# NN22_7Lvl_ResSrcAdapter02_s00.net
KiCad netlist of a schematic drawn in EAGLE
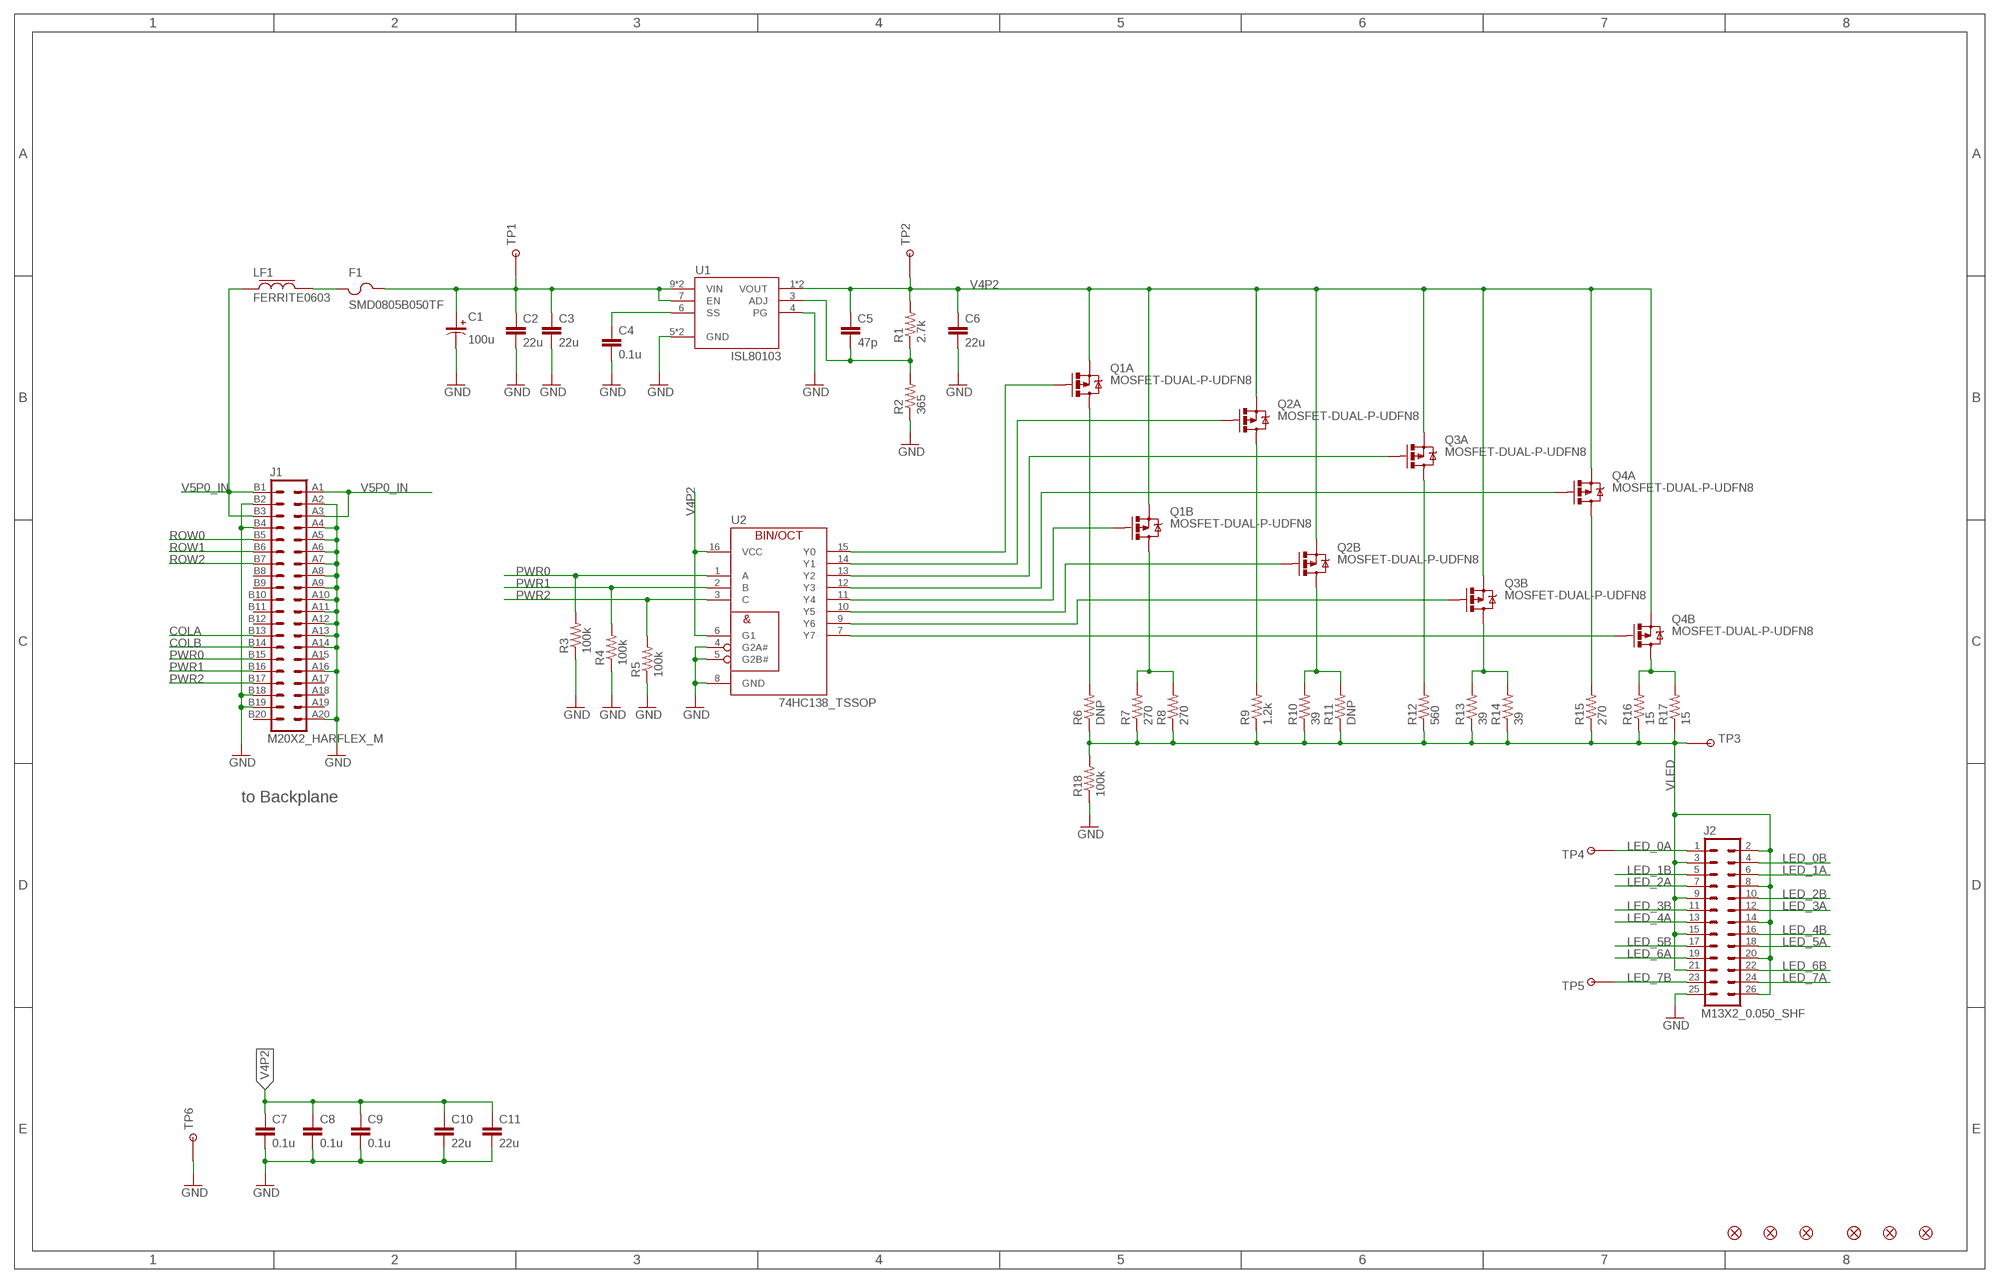
[diagram p0: schematic, sheet 1]
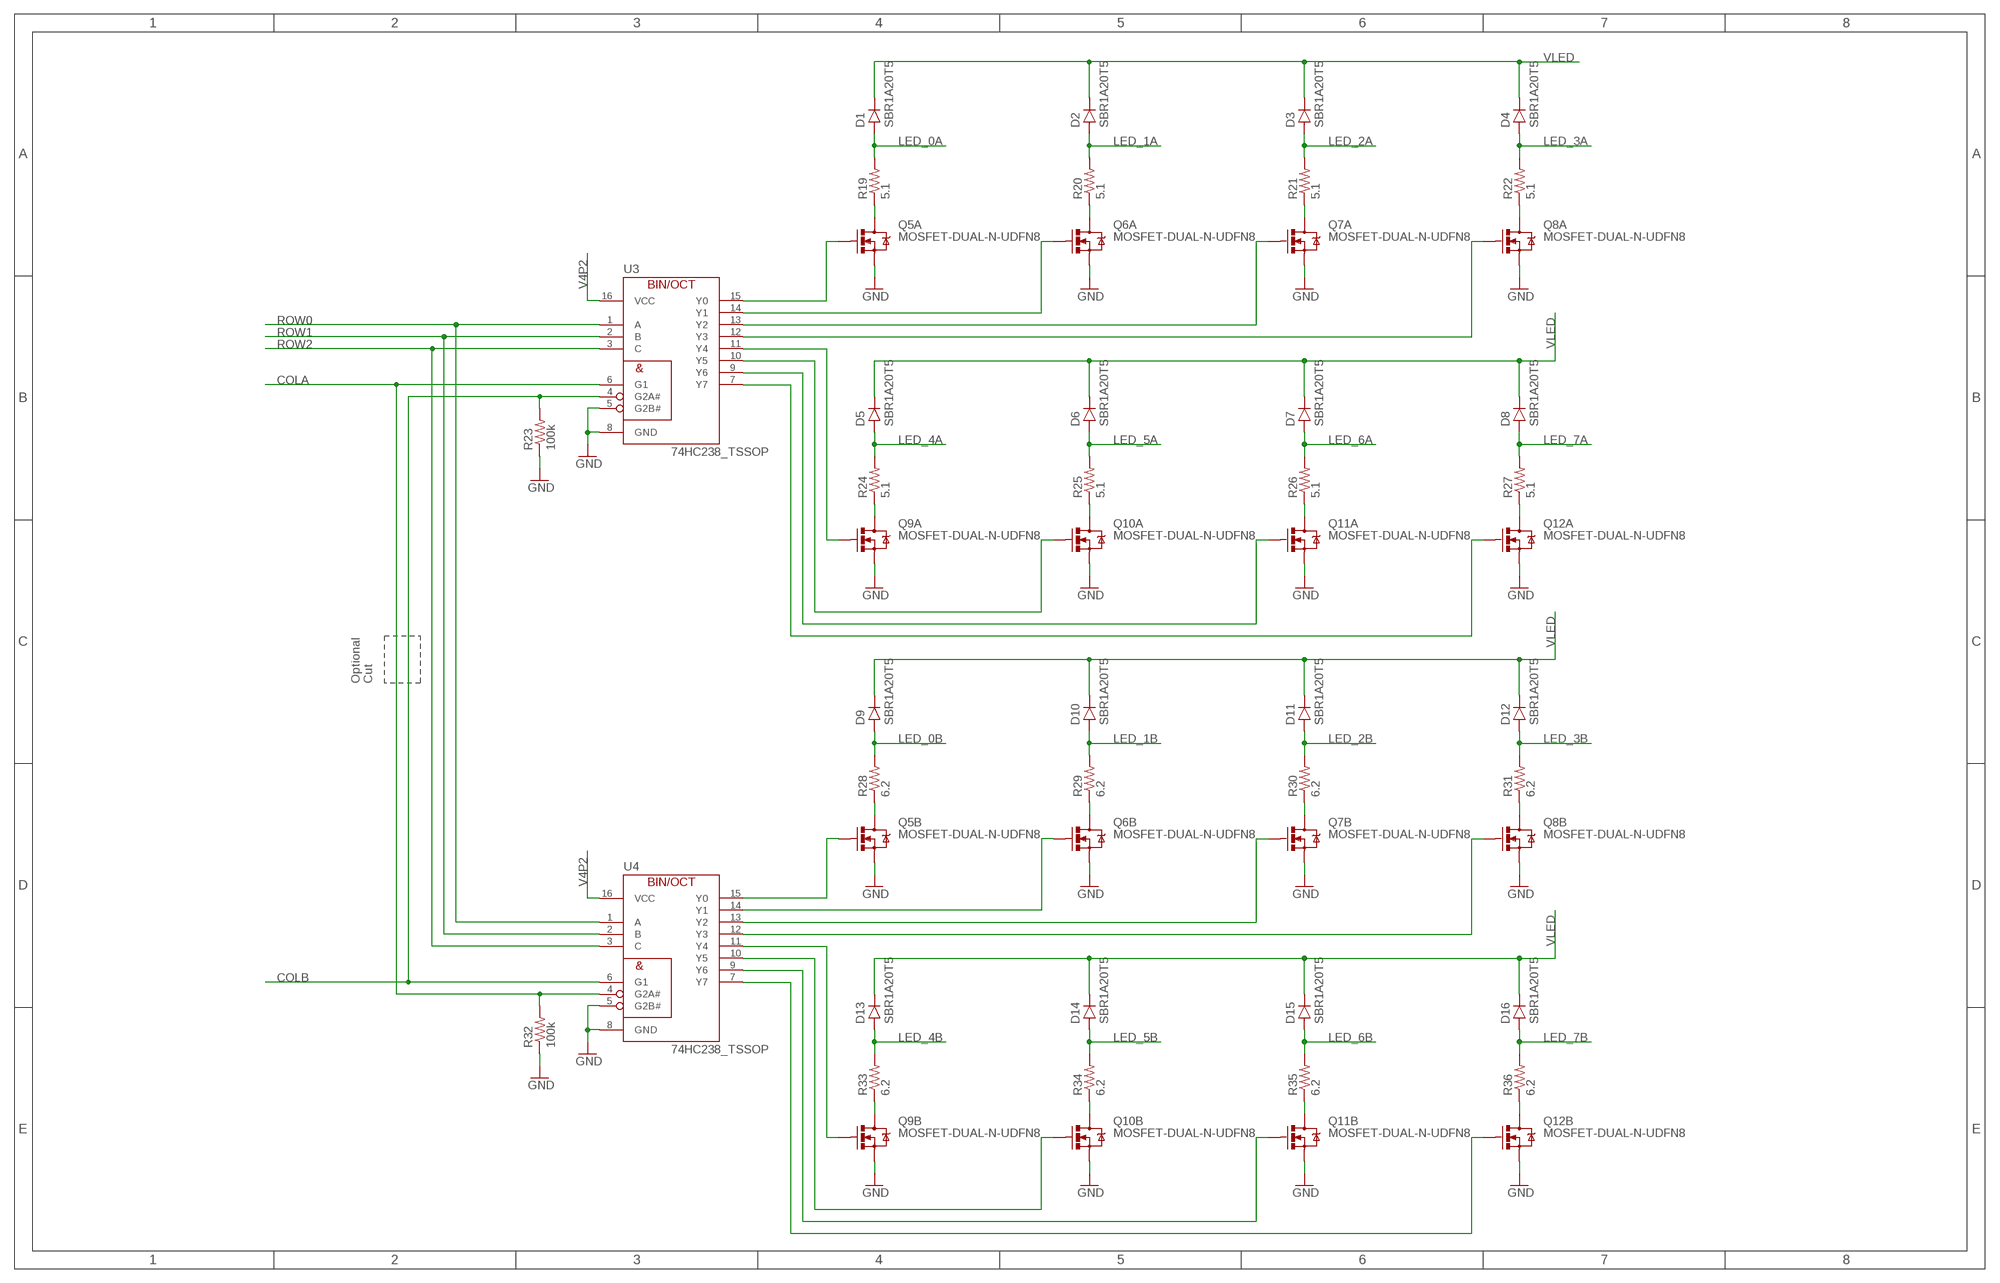
[diagram p1: schematic, sheet 2]

(export (version "E")
  (design (tool "Eeschema 10.0.6"))
  (components
    (comp (ref "D1")
      (value "SBR1A20T5")
      (footprint "eagle-import:SOD523")
      (libsource (lib "eagle-import") (part "DIODE_SOD523"))
    )
    (comp (ref "D2")
      (value "SBR1A20T5")
      (footprint "eagle-import:SOD523")
      (libsource (lib "eagle-import") (part "DIODE_SOD523"))
    )
    (comp (ref "D3")
      (value "SBR1A20T5")
      (footprint "eagle-import:SOD523")
      (libsource (lib "eagle-import") (part "DIODE_SOD523"))
    )
    (comp (ref "D4")
      (value "SBR1A20T5")
      (footprint "eagle-import:SOD523")
      (libsource (lib "eagle-import") (part "DIODE_SOD523"))
    )
    (comp (ref "D5")
      (value "SBR1A20T5")
      (footprint "eagle-import:SOD523")
      (libsource (lib "eagle-import") (part "DIODE_SOD523"))
    )
    (comp (ref "D6")
      (value "SBR1A20T5")
      (footprint "eagle-import:SOD523")
      (libsource (lib "eagle-import") (part "DIODE_SOD523"))
    )
    (comp (ref "D7")
      (value "SBR1A20T5")
      (footprint "eagle-import:SOD523")
      (libsource (lib "eagle-import") (part "DIODE_SOD523"))
    )
    (comp (ref "D8")
      (value "SBR1A20T5")
      (footprint "eagle-import:SOD523")
      (libsource (lib "eagle-import") (part "DIODE_SOD523"))
    )
    (comp (ref "D9")
      (value "SBR1A20T5")
      (footprint "eagle-import:SOD523")
      (libsource (lib "eagle-import") (part "DIODE_SOD523"))
    )
    (comp (ref "D10")
      (value "SBR1A20T5")
      (footprint "eagle-import:SOD523")
      (libsource (lib "eagle-import") (part "DIODE_SOD523"))
    )
    (comp (ref "D11")
      (value "SBR1A20T5")
      (footprint "eagle-import:SOD523")
      (libsource (lib "eagle-import") (part "DIODE_SOD523"))
    )
    (comp (ref "D12")
      (value "SBR1A20T5")
      (footprint "eagle-import:SOD523")
      (libsource (lib "eagle-import") (part "DIODE_SOD523"))
    )
    (comp (ref "D13")
      (value "SBR1A20T5")
      (footprint "eagle-import:SOD523")
      (libsource (lib "eagle-import") (part "DIODE_SOD523"))
    )
    (comp (ref "D14")
      (value "SBR1A20T5")
      (footprint "eagle-import:SOD523")
      (libsource (lib "eagle-import") (part "DIODE_SOD523"))
    )
    (comp (ref "D15")
      (value "SBR1A20T5")
      (footprint "eagle-import:SOD523")
      (libsource (lib "eagle-import") (part "DIODE_SOD523"))
    )
    (comp (ref "D16")
      (value "SBR1A20T5")
      (footprint "eagle-import:SOD523")
      (libsource (lib "eagle-import") (part "DIODE_SOD523"))
    )
    (comp (ref "Q5")
      (value "MOSFET-DUAL-N-UDFN8")
      (footprint "eagle-import:UDFN8")
      (libsource (lib "eagle-import") (part "MOSFET-DUAL-N-UDFN8"))
    )
    (comp (ref "Q6")
      (value "MOSFET-DUAL-N-UDFN8")
      (footprint "eagle-import:UDFN8")
      (libsource (lib "eagle-import") (part "MOSFET-DUAL-N-UDFN8"))
    )
    (comp (ref "Q7")
      (value "MOSFET-DUAL-N-UDFN8")
      (footprint "eagle-import:UDFN8")
      (libsource (lib "eagle-import") (part "MOSFET-DUAL-N-UDFN8"))
    )
    (comp (ref "Q8")
      (value "MOSFET-DUAL-N-UDFN8")
      (footprint "eagle-import:UDFN8")
      (libsource (lib "eagle-import") (part "MOSFET-DUAL-N-UDFN8"))
    )
    (comp (ref "Q9")
      (value "MOSFET-DUAL-N-UDFN8")
      (footprint "eagle-import:UDFN8")
      (libsource (lib "eagle-import") (part "MOSFET-DUAL-N-UDFN8"))
    )
    (comp (ref "Q10")
      (value "MOSFET-DUAL-N-UDFN8")
      (footprint "eagle-import:UDFN8")
      (libsource (lib "eagle-import") (part "MOSFET-DUAL-N-UDFN8"))
    )
    (comp (ref "Q11")
      (value "MOSFET-DUAL-N-UDFN8")
      (footprint "eagle-import:UDFN8")
      (libsource (lib "eagle-import") (part "MOSFET-DUAL-N-UDFN8"))
    )
    (comp (ref "Q12")
      (value "MOSFET-DUAL-N-UDFN8")
      (footprint "eagle-import:UDFN8")
      (libsource (lib "eagle-import") (part "MOSFET-DUAL-N-UDFN8"))
    )
    (comp (ref "R19")
      (value "5.1")
      (footprint "eagle-import:0805")
      (libsource (lib "eagle-import") (part "RESISTOR0805-RES"))
    )
    (comp (ref "R20")
      (value "5.1")
      (footprint "eagle-import:0805")
      (libsource (lib "eagle-import") (part "RESISTOR0805-RES"))
    )
    (comp (ref "R21")
      (value "5.1")
      (footprint "eagle-import:0805")
      (libsource (lib "eagle-import") (part "RESISTOR0805-RES"))
    )
    (comp (ref "R22")
      (value "5.1")
      (footprint "eagle-import:0805")
      (libsource (lib "eagle-import") (part "RESISTOR0805-RES"))
    )
    (comp (ref "R23")
      (value "100k")
      (footprint "eagle-import:0402-RES")
      (libsource (lib "eagle-import") (part "RESISTOR0402-RES"))
    )
    (comp (ref "R24")
      (value "5.1")
      (footprint "eagle-import:0805")
      (libsource (lib "eagle-import") (part "RESISTOR0805-RES"))
    )
    (comp (ref "R25")
      (value "5.1")
      (footprint "eagle-import:0805")
      (libsource (lib "eagle-import") (part "RESISTOR0805-RES"))
    )
    (comp (ref "R26")
      (value "5.1")
      (footprint "eagle-import:0805")
      (libsource (lib "eagle-import") (part "RESISTOR0805-RES"))
    )
    (comp (ref "R27")
      (value "5.1")
      (footprint "eagle-import:0805")
      (libsource (lib "eagle-import") (part "RESISTOR0805-RES"))
    )
    (comp (ref "R28")
      (value "6.2")
      (footprint "eagle-import:0805")
      (libsource (lib "eagle-import") (part "RESISTOR0805-RES"))
    )
    (comp (ref "R29")
      (value "6.2")
      (footprint "eagle-import:0805")
      (libsource (lib "eagle-import") (part "RESISTOR0805-RES"))
    )
    (comp (ref "R30")
      (value "6.2")
      (footprint "eagle-import:0805")
      (libsource (lib "eagle-import") (part "RESISTOR0805-RES"))
    )
    (comp (ref "R31")
      (value "6.2")
      (footprint "eagle-import:0805")
      (libsource (lib "eagle-import") (part "RESISTOR0805-RES"))
    )
    (comp (ref "R32")
      (value "100k")
      (footprint "eagle-import:0402-RES")
      (libsource (lib "eagle-import") (part "RESISTOR0402-RES"))
    )
    (comp (ref "R33")
      (value "6.2")
      (footprint "eagle-import:0805")
      (libsource (lib "eagle-import") (part "RESISTOR0805-RES"))
    )
    (comp (ref "R34")
      (value "6.2")
      (footprint "eagle-import:0805")
      (libsource (lib "eagle-import") (part "RESISTOR0805-RES"))
    )
    (comp (ref "R35")
      (value "6.2")
      (footprint "eagle-import:0805")
      (libsource (lib "eagle-import") (part "RESISTOR0805-RES"))
    )
    (comp (ref "R36")
      (value "6.2")
      (footprint "eagle-import:0805")
      (libsource (lib "eagle-import") (part "RESISTOR0805-RES"))
    )
    (comp (ref "U3")
      (value "74HC238_TSSOP")
      (footprint "eagle-import:TSSOP16")
      (libsource (lib "eagle-import") (part "74HC238_TSSOP"))
    )
    (comp (ref "U4")
      (value "74HC238_TSSOP")
      (footprint "eagle-import:TSSOP16")
      (libsource (lib "eagle-import") (part "74HC238_TSSOP"))
    )
    (comp (ref "C1")
      (value "100u")
      (footprint "eagle-import:2917-CAP")
      (libsource (lib "eagle-import") (part "CAP-POL2917"))
    )
    (comp (ref "C2")
      (value "22u")
      (footprint "eagle-import:1206")
      (libsource (lib "eagle-import") (part "CAP1206"))
    )
    (comp (ref "C3")
      (value "22u")
      (footprint "eagle-import:1206")
      (libsource (lib "eagle-import") (part "CAP1206"))
    )
    (comp (ref "C4")
      (value "0.1u")
      (footprint "eagle-import:0402-CAP")
      (libsource (lib "eagle-import") (part "CAP0402-CAP"))
    )
    (comp (ref "C5")
      (value "47p")
      (footprint "eagle-import:0402-CAP")
      (libsource (lib "eagle-import") (part "CAP0402-CAP"))
    )
    (comp (ref "C6")
      (value "22u")
      (footprint "eagle-import:1206")
      (libsource (lib "eagle-import") (part "CAP1206"))
    )
    (comp (ref "C7")
      (value "0.1u")
      (footprint "eagle-import:0402-CAP")
      (libsource (lib "eagle-import") (part "CAP0402-CAP"))
    )
    (comp (ref "C8")
      (value "0.1u")
      (footprint "eagle-import:0402-CAP")
      (libsource (lib "eagle-import") (part "CAP0402-CAP"))
    )
    (comp (ref "C9")
      (value "0.1u")
      (footprint "eagle-import:0402-CAP")
      (libsource (lib "eagle-import") (part "CAP0402-CAP"))
    )
    (comp (ref "C10")
      (value "22u")
      (footprint "eagle-import:1206")
      (libsource (lib "eagle-import") (part "CAP1206"))
    )
    (comp (ref "C11")
      (value "22u")
      (footprint "eagle-import:1206")
      (libsource (lib "eagle-import") (part "CAP1206"))
    )
    (comp (ref "F1")
      (value "SMD0805B050TF")
      (footprint "eagle-import:0805")
      (libsource (lib "eagle-import") (part "FUSE_0805"))
    )
    (comp (ref "FID1")
      (value "FIDUCIALUFIDUCIAL")
      (footprint "eagle-import:MICRO-FIDUCIAL")
      (libsource (lib "eagle-import") (part "FIDUCIALUFIDUCIAL"))
    )
    (comp (ref "FID2")
      (value "FIDUCIALUFIDUCIAL")
      (footprint "eagle-import:MICRO-FIDUCIAL")
      (libsource (lib "eagle-import") (part "FIDUCIALUFIDUCIAL"))
    )
    (comp (ref "FID3")
      (value "FIDUCIALUFIDUCIAL")
      (footprint "eagle-import:MICRO-FIDUCIAL")
      (libsource (lib "eagle-import") (part "FIDUCIALUFIDUCIAL"))
    )
    (comp (ref "FID4")
      (value "FIDUCIALUFIDUCIAL")
      (footprint "eagle-import:MICRO-FIDUCIAL")
      (libsource (lib "eagle-import") (part "FIDUCIALUFIDUCIAL"))
    )
    (comp (ref "FID5")
      (value "FIDUCIALUFIDUCIAL")
      (footprint "eagle-import:MICRO-FIDUCIAL")
      (libsource (lib "eagle-import") (part "FIDUCIALUFIDUCIAL"))
    )
    (comp (ref "FID6")
      (value "FIDUCIALUFIDUCIAL")
      (footprint "eagle-import:MICRO-FIDUCIAL")
      (libsource (lib "eagle-import") (part "FIDUCIALUFIDUCIAL"))
    )
    (comp (ref "J1")
      (value "M20X2_HARFLEX_M")
      (footprint "eagle-import:M20X2_HARFLEX_M")
      (libsource (lib "eagle-import") (part "M20X2_HARFLEX_M"))
    )
    (comp (ref "J2")
      (value "M13X2_0.050_SHF")
      (footprint "eagle-import:M13X2_0.050_SHF")
      (libsource (lib "eagle-import") (part "M13X2_0.050_SHF"))
    )
    (comp (ref "LF1")
      (value "FERRITE0603")
      (footprint "eagle-import:0603-FER")
      (libsource (lib "eagle-import") (part "FERRITE0603"))
    )
    (comp (ref "Q1")
      (value "MOSFET-DUAL-P-UDFN8")
      (footprint "eagle-import:UDFN8")
      (libsource (lib "eagle-import") (part "MOSFET-DUAL-P-UDFN8"))
    )
    (comp (ref "Q2")
      (value "MOSFET-DUAL-P-UDFN8")
      (footprint "eagle-import:UDFN8")
      (libsource (lib "eagle-import") (part "MOSFET-DUAL-P-UDFN8"))
    )
    (comp (ref "Q3")
      (value "MOSFET-DUAL-P-UDFN8")
      (footprint "eagle-import:UDFN8")
      (libsource (lib "eagle-import") (part "MOSFET-DUAL-P-UDFN8"))
    )
    (comp (ref "Q4")
      (value "MOSFET-DUAL-P-UDFN8")
      (footprint "eagle-import:UDFN8")
      (libsource (lib "eagle-import") (part "MOSFET-DUAL-P-UDFN8"))
    )
    (comp (ref "R1")
      (value "2.7k")
      (footprint "eagle-import:0402-RES")
      (libsource (lib "eagle-import") (part "RESISTOR0402-RES"))
    )
    (comp (ref "R2")
      (value "365")
      (footprint "eagle-import:0402-RES")
      (libsource (lib "eagle-import") (part "RESISTOR0402-RES"))
    )
    (comp (ref "R3")
      (value "100k")
      (footprint "eagle-import:0402-RES")
      (libsource (lib "eagle-import") (part "RESISTOR0402-RES"))
    )
    (comp (ref "R4")
      (value "100k")
      (footprint "eagle-import:0402-RES")
      (libsource (lib "eagle-import") (part "RESISTOR0402-RES"))
    )
    (comp (ref "R5")
      (value "100k")
      (footprint "eagle-import:0402-RES")
      (libsource (lib "eagle-import") (part "RESISTOR0402-RES"))
    )
    (comp (ref "R6")
      (value "DNP")
      (footprint "eagle-import:0805")
      (libsource (lib "eagle-import") (part "RESISTOR0805-RES"))
    )
    (comp (ref "R7")
      (value "270")
      (footprint "eagle-import:0805")
      (libsource (lib "eagle-import") (part "RESISTOR0805-RES"))
    )
    (comp (ref "R8")
      (value "270")
      (footprint "eagle-import:0805")
      (libsource (lib "eagle-import") (part "RESISTOR0805-RES"))
    )
    (comp (ref "R9")
      (value "1.2k")
      (footprint "eagle-import:0805")
      (libsource (lib "eagle-import") (part "RESISTOR0805-RES"))
    )
    (comp (ref "R10")
      (value "39")
      (footprint "eagle-import:0805")
      (libsource (lib "eagle-import") (part "RESISTOR0805-RES"))
    )
    (comp (ref "R11")
      (value "DNP")
      (footprint "eagle-import:0805")
      (libsource (lib "eagle-import") (part "RESISTOR0805-RES"))
    )
    (comp (ref "R12")
      (value "560")
      (footprint "eagle-import:0805")
      (libsource (lib "eagle-import") (part "RESISTOR0805-RES"))
    )
    (comp (ref "R13")
      (value "39")
      (footprint "eagle-import:0805")
      (libsource (lib "eagle-import") (part "RESISTOR0805-RES"))
    )
    (comp (ref "R14")
      (value "39")
      (footprint "eagle-import:0805")
      (libsource (lib "eagle-import") (part "RESISTOR0805-RES"))
    )
    (comp (ref "R15")
      (value "270")
      (footprint "eagle-import:0805")
      (libsource (lib "eagle-import") (part "RESISTOR0805-RES"))
    )
    (comp (ref "R16")
      (value "15")
      (footprint "eagle-import:0805")
      (libsource (lib "eagle-import") (part "RESISTOR0805-RES"))
    )
    (comp (ref "R17")
      (value "15")
      (footprint "eagle-import:0805")
      (libsource (lib "eagle-import") (part "RESISTOR0805-RES"))
    )
    (comp (ref "R18")
      (value "100k")
      (footprint "eagle-import:0402-RES")
      (libsource (lib "eagle-import") (part "RESISTOR0402-RES"))
    )
    (comp (ref "TP1")
      (value "TESTPOINT_ROUND")
      (footprint "eagle-import:TESTPAD_ROUND")
      (libsource (lib "eagle-import") (part "TESTPOINT_ROUND"))
    )
    (comp (ref "TP2")
      (value "TESTPOINT_ROUND")
      (footprint "eagle-import:TESTPAD_ROUND")
      (libsource (lib "eagle-import") (part "TESTPOINT_ROUND"))
    )
    (comp (ref "TP3")
      (value "TESTPOINT_ROUND")
      (footprint "eagle-import:TESTPAD_ROUND")
      (libsource (lib "eagle-import") (part "TESTPOINT_ROUND"))
    )
    (comp (ref "TP4")
      (value "TESTPOINT_ROUND")
      (footprint "eagle-import:TESTPAD_ROUND")
      (libsource (lib "eagle-import") (part "TESTPOINT_ROUND"))
    )
    (comp (ref "TP5")
      (value "TESTPOINT_ROUND")
      (footprint "eagle-import:TESTPAD_ROUND")
      (libsource (lib "eagle-import") (part "TESTPOINT_ROUND"))
    )
    (comp (ref "TP6")
      (value "TESTPOINT1X01")
      (footprint "eagle-import:1X01")
      (libsource (lib "eagle-import") (part "TESTPOINT1X01"))
    )
    (comp (ref "U1")
      (value "ISL80103")
      (footprint "eagle-import:DFN10_ISL")
      (libsource (lib "eagle-import") (part "ISL80103"))
    )
    (comp (ref "U2")
      (value "74HC138_TSSOP")
      (footprint "eagle-import:TSSOP16")
      (libsource (lib "eagle-import") (part "74HC138_TSSOP"))
    )
  )
  (nets
    (net (code "1") (name "COLA") (class "Default")
      (node (ref "J1") (pin "B13") (pinfunction "25_B13") (pintype "passive"))
      (node (ref "R32") (pin "2") (pinfunction "2_2") (pintype "passive"))
      (node (ref "U3") (pin "6") (pinfunction "G1_6") (pintype "input"))
      (node (ref "U4") (pin "4") (pinfunction "G2A#_4") (pintype "input"))
    )
    (net (code "2") (name "COLB") (class "Default")
      (node (ref "J1") (pin "B14") (pinfunction "27_B14") (pintype "passive"))
      (node (ref "R23") (pin "2") (pinfunction "2_2") (pintype "passive"))
      (node (ref "U3") (pin "4") (pinfunction "G2A#_4") (pintype "input"))
      (node (ref "U4") (pin "6") (pinfunction "G1_6") (pintype "input"))
    )
    (net (code "3") (name "GND") (class "Default")
      (node (ref "C1") (pin "N") (pinfunction "N_N") (pintype "passive"))
      (node (ref "C10") (pin "2") (pinfunction "2_2") (pintype "passive"))
      (node (ref "C11") (pin "2") (pinfunction "2_2") (pintype "passive"))
      (node (ref "C2") (pin "2") (pinfunction "2_2") (pintype "passive"))
      (node (ref "C3") (pin "2") (pinfunction "2_2") (pintype "passive"))
      (node (ref "C4") (pin "2") (pinfunction "2_2") (pintype "passive"))
      (node (ref "C6") (pin "2") (pinfunction "2_2") (pintype "passive"))
      (node (ref "C7") (pin "2") (pinfunction "2_2") (pintype "passive"))
      (node (ref "C8") (pin "2") (pinfunction "2_2") (pintype "passive"))
      (node (ref "C9") (pin "2") (pinfunction "2_2") (pintype "passive"))
      (node (ref "J1") (pin "A10") (pinfunction "20_A10") (pintype "passive"))
      (node (ref "J1") (pin "A11") (pinfunction "22_A11") (pintype "passive"))
      (node (ref "J1") (pin "A12") (pinfunction "24_A12") (pintype "passive"))
      (node (ref "J1") (pin "A13") (pinfunction "26_A13") (pintype "passive"))
      (node (ref "J1") (pin "A14") (pinfunction "28_A14") (pintype "passive"))
      (node (ref "J1") (pin "A16") (pinfunction "32_A16") (pintype "passive"))
      (node (ref "J1") (pin "A2") (pinfunction "4_A2") (pintype "passive"))
      (node (ref "J1") (pin "A20") (pinfunction "40_A20") (pintype "passive"))
      (node (ref "J1") (pin "A4") (pinfunction "8_A4") (pintype "passive"))
      (node (ref "J1") (pin "A5") (pinfunction "10_A5") (pintype "passive"))
      (node (ref "J1") (pin "A6") (pinfunction "12_A6") (pintype "passive"))
      (node (ref "J1") (pin "A7") (pinfunction "14_A7") (pintype "passive"))
      (node (ref "J1") (pin "A8") (pinfunction "16_A8") (pintype "passive"))
      (node (ref "J1") (pin "A9") (pinfunction "18_A9") (pintype "passive"))
      (node (ref "J1") (pin "B18") (pinfunction "35_B18") (pintype "passive"))
      (node (ref "J1") (pin "B19") (pinfunction "37_B19") (pintype "passive"))
      (node (ref "J1") (pin "B2") (pinfunction "3_B2") (pintype "passive"))
      (node (ref "J1") (pin "B4") (pinfunction "7_B4") (pintype "passive"))
      (node (ref "J2") (pin "25") (pinfunction "25_25") (pintype "passive"))
      (node (ref "Q10") (pin "1") (pinfunction "S_1") (pintype "passive"))
      (node (ref "Q10") (pin "4") (pinfunction "S_4") (pintype "passive"))
      (node (ref "Q11") (pin "1") (pinfunction "S_1") (pintype "passive"))
      (node (ref "Q11") (pin "4") (pinfunction "S_4") (pintype "passive"))
      (node (ref "Q12") (pin "1") (pinfunction "S_1") (pintype "passive"))
      (node (ref "Q12") (pin "4") (pinfunction "S_4") (pintype "passive"))
      (node (ref "Q5") (pin "1") (pinfunction "S_1") (pintype "passive"))
      (node (ref "Q5") (pin "4") (pinfunction "S_4") (pintype "passive"))
      (node (ref "Q6") (pin "1") (pinfunction "S_1") (pintype "passive"))
      (node (ref "Q6") (pin "4") (pinfunction "S_4") (pintype "passive"))
      (node (ref "Q7") (pin "1") (pinfunction "S_1") (pintype "passive"))
      (node (ref "Q7") (pin "4") (pinfunction "S_4") (pintype "passive"))
      (node (ref "Q8") (pin "1") (pinfunction "S_1") (pintype "passive"))
      (node (ref "Q8") (pin "4") (pinfunction "S_4") (pintype "passive"))
      (node (ref "Q9") (pin "1") (pinfunction "S_1") (pintype "passive"))
      (node (ref "Q9") (pin "4") (pinfunction "S_4") (pintype "passive"))
      (node (ref "R18") (pin "1") (pinfunction "1_1") (pintype "passive"))
      (node (ref "R2") (pin "1") (pinfunction "1_1") (pintype "passive"))
      (node (ref "R23") (pin "1") (pinfunction "1_1") (pintype "passive"))
      (node (ref "R3") (pin "1") (pinfunction "1_1") (pintype "passive"))
      (node (ref "R32") (pin "1") (pinfunction "1_1") (pintype "passive"))
      (node (ref "R4") (pin "1") (pinfunction "1_1") (pintype "passive"))
      (node (ref "R5") (pin "1") (pinfunction "1_1") (pintype "passive"))
      (node (ref "TP6") (pin "1") (pinfunction "P$1_1") (pintype "bidirectional"))
      (node (ref "U1") (pin "4") (pinfunction "PG_4") (pintype "open_collector"))
      (node (ref "U1") (pin "5") (pinfunction "GND_5") (pintype "power_in"))
      (node (ref "U1") (pin "PAD") (pinfunction "GND_PAD") (pintype "power_in"))
      (node (ref "U2") (pin "4") (pinfunction "G2A#_4") (pintype "input"))
      (node (ref "U2") (pin "5") (pinfunction "G2B#_5") (pintype "input"))
      (node (ref "U2") (pin "8") (pinfunction "GND_8") (pintype "power_in"))
      (node (ref "U3") (pin "5") (pinfunction "G2B#_5") (pintype "input"))
      (node (ref "U3") (pin "8") (pinfunction "GND_8") (pintype "power_in"))
      (node (ref "U4") (pin "5") (pinfunction "G2B#_5") (pintype "input"))
      (node (ref "U4") (pin "8") (pinfunction "GND_8") (pintype "power_in"))
    )
    (net (code "4") (name "LED_0A") (class "Default")
      (node (ref "D1") (pin "A") (pinfunction "A_A") (pintype "bidirectional"))
      (node (ref "J2") (pin "1") (pinfunction "1_1") (pintype "passive"))
      (node (ref "R19") (pin "2") (pinfunction "2_2") (pintype "passive"))
      (node (ref "TP4") (pin "P$1") (pinfunction "P$1_P$1") (pintype "bidirectional"))
    )
    (net (code "5") (name "LED_0B") (class "Default")
      (node (ref "D9") (pin "A") (pinfunction "A_A") (pintype "bidirectional"))
      (node (ref "J2") (pin "4") (pinfunction "4_4") (pintype "passive"))
      (node (ref "R28") (pin "2") (pinfunction "2_2") (pintype "passive"))
    )
    (net (code "6") (name "LED_1A") (class "Default")
      (node (ref "D2") (pin "A") (pinfunction "A_A") (pintype "bidirectional"))
      (node (ref "J2") (pin "6") (pinfunction "6_6") (pintype "passive"))
      (node (ref "R20") (pin "2") (pinfunction "2_2") (pintype "passive"))
    )
    (net (code "7") (name "LED_1B") (class "Default")
      (node (ref "D10") (pin "A") (pinfunction "A_A") (pintype "bidirectional"))
      (node (ref "J2") (pin "5") (pinfunction "5_5") (pintype "passive"))
      (node (ref "R29") (pin "2") (pinfunction "2_2") (pintype "passive"))
    )
    (net (code "8") (name "LED_2A") (class "Default")
      (node (ref "D3") (pin "A") (pinfunction "A_A") (pintype "bidirectional"))
      (node (ref "J2") (pin "7") (pinfunction "7_7") (pintype "passive"))
      (node (ref "R21") (pin "2") (pinfunction "2_2") (pintype "passive"))
    )
    (net (code "9") (name "LED_2B") (class "Default")
      (node (ref "D11") (pin "A") (pinfunction "A_A") (pintype "bidirectional"))
      (node (ref "J2") (pin "10") (pinfunction "10_10") (pintype "passive"))
      (node (ref "R30") (pin "2") (pinfunction "2_2") (pintype "passive"))
    )
    (net (code "10") (name "LED_3A") (class "Default")
      (node (ref "D4") (pin "A") (pinfunction "A_A") (pintype "bidirectional"))
      (node (ref "J2") (pin "12") (pinfunction "12_12") (pintype "passive"))
      (node (ref "R22") (pin "2") (pinfunction "2_2") (pintype "passive"))
    )
    (net (code "11") (name "LED_3B") (class "Default")
      (node (ref "D12") (pin "A") (pinfunction "A_A") (pintype "bidirectional"))
      (node (ref "J2") (pin "11") (pinfunction "11_11") (pintype "passive"))
      (node (ref "R31") (pin "2") (pinfunction "2_2") (pintype "passive"))
    )
    (net (code "12") (name "LED_4A") (class "Default")
      (node (ref "D5") (pin "A") (pinfunction "A_A") (pintype "bidirectional"))
      (node (ref "J2") (pin "13") (pinfunction "13_13") (pintype "passive"))
      (node (ref "R24") (pin "2") (pinfunction "2_2") (pintype "passive"))
    )
    (net (code "13") (name "LED_4B") (class "Default")
      (node (ref "D13") (pin "A") (pinfunction "A_A") (pintype "bidirectional"))
      (node (ref "J2") (pin "16") (pinfunction "16_16") (pintype "passive"))
      (node (ref "R33") (pin "2") (pinfunction "2_2") (pintype "passive"))
    )
    (net (code "14") (name "LED_5A") (class "Default")
      (node (ref "D6") (pin "A") (pinfunction "A_A") (pintype "bidirectional"))
      (node (ref "J2") (pin "18") (pinfunction "18_18") (pintype "passive"))
      (node (ref "R25") (pin "2") (pinfunction "2_2") (pintype "passive"))
    )
    (net (code "15") (name "LED_5B") (class "Default")
      (node (ref "D14") (pin "A") (pinfunction "A_A") (pintype "bidirectional"))
      (node (ref "J2") (pin "17") (pinfunction "17_17") (pintype "passive"))
      (node (ref "R34") (pin "2") (pinfunction "2_2") (pintype "passive"))
    )
    (net (code "16") (name "LED_6A") (class "Default")
      (node (ref "D7") (pin "A") (pinfunction "A_A") (pintype "bidirectional"))
      (node (ref "J2") (pin "19") (pinfunction "19_19") (pintype "passive"))
      (node (ref "R26") (pin "2") (pinfunction "2_2") (pintype "passive"))
    )
    (net (code "17") (name "LED_6B") (class "Default")
      (node (ref "D15") (pin "A") (pinfunction "A_A") (pintype "bidirectional"))
      (node (ref "J2") (pin "22") (pinfunction "22_22") (pintype "passive"))
      (node (ref "R35") (pin "2") (pinfunction "2_2") (pintype "passive"))
    )
    (net (code "18") (name "LED_7A") (class "Default")
      (node (ref "D8") (pin "A") (pinfunction "A_A") (pintype "bidirectional"))
      (node (ref "J2") (pin "24") (pinfunction "24_24") (pintype "passive"))
      (node (ref "R27") (pin "2") (pinfunction "2_2") (pintype "passive"))
    )
    (net (code "19") (name "LED_7B") (class "Default")
      (node (ref "D16") (pin "A") (pinfunction "A_A") (pintype "bidirectional"))
      (node (ref "J2") (pin "23") (pinfunction "23_23") (pintype "passive"))
      (node (ref "R36") (pin "2") (pinfunction "2_2") (pintype "passive"))
      (node (ref "TP5") (pin "P$1") (pinfunction "P$1_P$1") (pintype "bidirectional"))
    )
    (net (code "20") (name "Net-(LF1-P$2)") (class "Default")
      (node (ref "F1") (pin "1") (pinfunction "1_1") (pintype "bidirectional"))
      (node (ref "LF1") (pin "2") (pinfunction "P$2_2") (pintype "bidirectional"))
    )
    (net (code "21") (name "Net-(Q1A-D-Pad6)") (class "Default")
      (node (ref "Q1") (pin "6") (pinfunction "D_6") (pintype "passive"))
      (node (ref "Q1") (pin "P1") (pinfunction "D_P1") (pintype "passive"))
      (node (ref "R6") (pin "2") (pinfunction "2_2") (pintype "passive"))
    )
    (net (code "22") (name "Net-(Q1A-G)") (class "Default")
      (node (ref "Q1") (pin "2") (pinfunction "G_2") (pintype "passive"))
      (node (ref "U2") (pin "15") (pinfunction "Y0_15") (pintype "output"))
    )
    (net (code "23") (name "Net-(Q1B-D-Pad3)") (class "Default")
      (node (ref "Q1") (pin "3") (pinfunction "D_3") (pintype "passive"))
      (node (ref "Q1") (pin "P2") (pinfunction "D_P2") (pintype "passive"))
      (node (ref "R7") (pin "2") (pinfunction "2_2") (pintype "passive"))
      (node (ref "R8") (pin "2") (pinfunction "2_2") (pintype "passive"))
    )
    (net (code "24") (name "Net-(Q1B-G)") (class "Default")
      (node (ref "Q1") (pin "5") (pinfunction "G_5") (pintype "passive"))
      (node (ref "U2") (pin "11") (pinfunction "Y4_11") (pintype "output"))
    )
    (net (code "25") (name "Net-(Q2A-D-Pad6)") (class "Default")
      (node (ref "Q2") (pin "6") (pinfunction "D_6") (pintype "passive"))
      (node (ref "Q2") (pin "P1") (pinfunction "D_P1") (pintype "passive"))
      (node (ref "R9") (pin "2") (pinfunction "2_2") (pintype "passive"))
    )
    (net (code "26") (name "Net-(Q2A-G)") (class "Default")
      (node (ref "Q2") (pin "2") (pinfunction "G_2") (pintype "passive"))
      (node (ref "U2") (pin "14") (pinfunction "Y1_14") (pintype "output"))
    )
    (net (code "27") (name "Net-(Q2B-D-Pad3)") (class "Default")
      (node (ref "Q2") (pin "3") (pinfunction "D_3") (pintype "passive"))
      (node (ref "Q2") (pin "P2") (pinfunction "D_P2") (pintype "passive"))
      (node (ref "R10") (pin "2") (pinfunction "2_2") (pintype "passive"))
      (node (ref "R11") (pin "2") (pinfunction "2_2") (pintype "passive"))
    )
    (net (code "28") (name "Net-(Q2B-G)") (class "Default")
      (node (ref "Q2") (pin "5") (pinfunction "G_5") (pintype "passive"))
      (node (ref "U2") (pin "10") (pinfunction "Y5_10") (pintype "output"))
    )
    (net (code "29") (name "Net-(Q3A-D-Pad6)") (class "Default")
      (node (ref "Q3") (pin "6") (pinfunction "D_6") (pintype "passive"))
      (node (ref "Q3") (pin "P1") (pinfunction "D_P1") (pintype "passive"))
      (node (ref "R12") (pin "2") (pinfunction "2_2") (pintype "passive"))
    )
    (net (code "30") (name "Net-(Q3A-G)") (class "Default")
      (node (ref "Q3") (pin "2") (pinfunction "G_2") (pintype "passive"))
      (node (ref "U2") (pin "13") (pinfunction "Y2_13") (pintype "output"))
    )
    (net (code "31") (name "Net-(Q3B-D-Pad3)") (class "Default")
      (node (ref "Q3") (pin "3") (pinfunction "D_3") (pintype "passive"))
      (node (ref "Q3") (pin "P2") (pinfunction "D_P2") (pintype "passive"))
      (node (ref "R13") (pin "2") (pinfunction "2_2") (pintype "passive"))
      (node (ref "R14") (pin "2") (pinfunction "2_2") (pintype "passive"))
    )
    (net (code "32") (name "Net-(Q3B-G)") (class "Default")
      (node (ref "Q3") (pin "5") (pinfunction "G_5") (pintype "passive"))
      (node (ref "U2") (pin "9") (pinfunction "Y6_9") (pintype "output"))
    )
    (net (code "33") (name "Net-(Q4A-D-Pad6)") (class "Default")
      (node (ref "Q4") (pin "6") (pinfunction "D_6") (pintype "passive"))
      (node (ref "Q4") (pin "P1") (pinfunction "D_P1") (pintype "passive"))
      (node (ref "R15") (pin "2") (pinfunction "2_2") (pintype "passive"))
    )
    (net (code "34") (name "Net-(Q4A-G)") (class "Default")
      (node (ref "Q4") (pin "2") (pinfunction "G_2") (pintype "passive"))
      (node (ref "U2") (pin "12") (pinfunction "Y3_12") (pintype "output"))
    )
    (net (code "35") (name "Net-(Q4B-D-Pad3)") (class "Default")
      (node (ref "Q4") (pin "3") (pinfunction "D_3") (pintype "passive"))
      (node (ref "Q4") (pin "P2") (pinfunction "D_P2") (pintype "passive"))
      (node (ref "R16") (pin "2") (pinfunction "2_2") (pintype "passive"))
      (node (ref "R17") (pin "2") (pinfunction "2_2") (pintype "passive"))
    )
    (net (code "36") (name "Net-(Q4B-G)") (class "Default")
      (node (ref "Q4") (pin "5") (pinfunction "G_5") (pintype "passive"))
      (node (ref "U2") (pin "7") (pinfunction "Y7_7") (pintype "output"))
    )
    (net (code "37") (name "Net-(Q5A-D-Pad6)") (class "Default")
      (node (ref "Q5") (pin "6") (pinfunction "D_6") (pintype "passive"))
      (node (ref "Q5") (pin "P1") (pinfunction "D_P1") (pintype "passive"))
      (node (ref "R19") (pin "1") (pinfunction "1_1") (pintype "passive"))
    )
    (net (code "38") (name "Net-(Q5A-G)") (class "Default")
      (node (ref "Q5") (pin "2") (pinfunction "G_2") (pintype "passive"))
      (node (ref "U3") (pin "15") (pinfunction "Y0_15") (pintype "output"))
    )
    (net (code "39") (name "Net-(Q5B-D-Pad3)") (class "Default")
      (node (ref "Q5") (pin "3") (pinfunction "D_3") (pintype "passive"))
      (node (ref "Q5") (pin "P2") (pinfunction "D_P2") (pintype "passive"))
      (node (ref "R28") (pin "1") (pinfunction "1_1") (pintype "passive"))
    )
    (net (code "40") (name "Net-(Q5B-G)") (class "Default")
      (node (ref "Q5") (pin "5") (pinfunction "G_5") (pintype "passive"))
      (node (ref "U4") (pin "15") (pinfunction "Y0_15") (pintype "output"))
    )
    (net (code "41") (name "Net-(Q6A-D-Pad6)") (class "Default")
      (node (ref "Q6") (pin "6") (pinfunction "D_6") (pintype "passive"))
      (node (ref "Q6") (pin "P1") (pinfunction "D_P1") (pintype "passive"))
      (node (ref "R20") (pin "1") (pinfunction "1_1") (pintype "passive"))
    )
    (net (code "42") (name "Net-(Q6A-G)") (class "Default")
      (node (ref "Q6") (pin "2") (pinfunction "G_2") (pintype "passive"))
      (node (ref "U3") (pin "14") (pinfunction "Y1_14") (pintype "output"))
    )
    (net (code "43") (name "Net-(Q6B-D-Pad3)") (class "Default")
      (node (ref "Q6") (pin "3") (pinfunction "D_3") (pintype "passive"))
      (node (ref "Q6") (pin "P2") (pinfunction "D_P2") (pintype "passive"))
      (node (ref "R29") (pin "1") (pinfunction "1_1") (pintype "passive"))
    )
    (net (code "44") (name "Net-(Q6B-G)") (class "Default")
      (node (ref "Q6") (pin "5") (pinfunction "G_5") (pintype "passive"))
      (node (ref "U4") (pin "14") (pinfunction "Y1_14") (pintype "output"))
    )
    (net (code "45") (name "Net-(Q7A-D-Pad6)") (class "Default")
      (node (ref "Q7") (pin "6") (pinfunction "D_6") (pintype "passive"))
      (node (ref "Q7") (pin "P1") (pinfunction "D_P1") (pintype "passive"))
      (node (ref "R21") (pin "1") (pinfunction "1_1") (pintype "passive"))
    )
    (net (code "46") (name "Net-(Q7A-G)") (class "Default")
      (node (ref "Q7") (pin "2") (pinfunction "G_2") (pintype "passive"))
      (node (ref "U3") (pin "13") (pinfunction "Y2_13") (pintype "output"))
    )
    (net (code "47") (name "Net-(Q7B-D-Pad3)") (class "Default")
      (node (ref "Q7") (pin "3") (pinfunction "D_3") (pintype "passive"))
      (node (ref "Q7") (pin "P2") (pinfunction "D_P2") (pintype "passive"))
      (node (ref "R30") (pin "1") (pinfunction "1_1") (pintype "passive"))
    )
    (net (code "48") (name "Net-(Q7B-G)") (class "Default")
      (node (ref "Q7") (pin "5") (pinfunction "G_5") (pintype "passive"))
      (node (ref "U4") (pin "13") (pinfunction "Y2_13") (pintype "output"))
    )
    (net (code "49") (name "Net-(Q8A-D-Pad6)") (class "Default")
      (node (ref "Q8") (pin "6") (pinfunction "D_6") (pintype "passive"))
      (node (ref "Q8") (pin "P1") (pinfunction "D_P1") (pintype "passive"))
      (node (ref "R22") (pin "1") (pinfunction "1_1") (pintype "passive"))
    )
    (net (code "50") (name "Net-(Q8A-G)") (class "Default")
      (node (ref "Q8") (pin "2") (pinfunction "G_2") (pintype "passive"))
      (node (ref "U3") (pin "12") (pinfunction "Y3_12") (pintype "output"))
    )
    (net (code "51") (name "Net-(Q8B-D-Pad3)") (class "Default")
      (node (ref "Q8") (pin "3") (pinfunction "D_3") (pintype "passive"))
      (node (ref "Q8") (pin "P2") (pinfunction "D_P2") (pintype "passive"))
      (node (ref "R31") (pin "1") (pinfunction "1_1") (pintype "passive"))
    )
    (net (code "52") (name "Net-(Q8B-G)") (class "Default")
      (node (ref "Q8") (pin "5") (pinfunction "G_5") (pintype "passive"))
      (node (ref "U4") (pin "12") (pinfunction "Y3_12") (pintype "output"))
    )
    (net (code "53") (name "Net-(Q9A-D-Pad6)") (class "Default")
      (node (ref "Q9") (pin "6") (pinfunction "D_6") (pintype "passive"))
      (node (ref "Q9") (pin "P1") (pinfunction "D_P1") (pintype "passive"))
      (node (ref "R24") (pin "1") (pinfunction "1_1") (pintype "passive"))
    )
    (net (code "54") (name "Net-(Q9A-G)") (class "Default")
      (node (ref "Q9") (pin "2") (pinfunction "G_2") (pintype "passive"))
      (node (ref "U3") (pin "11") (pinfunction "Y4_11") (pintype "output"))
    )
    (net (code "55") (name "Net-(Q9B-D-Pad3)") (class "Default")
      (node (ref "Q9") (pin "3") (pinfunction "D_3") (pintype "passive"))
      (node (ref "Q9") (pin "P2") (pinfunction "D_P2") (pintype "passive"))
      (node (ref "R33") (pin "1") (pinfunction "1_1") (pintype "passive"))
    )
    (net (code "56") (name "Net-(Q9B-G)") (class "Default")
      (node (ref "Q9") (pin "5") (pinfunction "G_5") (pintype "passive"))
      (node (ref "U4") (pin "11") (pinfunction "Y4_11") (pintype "output"))
    )
    (net (code "57") (name "Net-(Q10A-D-Pad6)") (class "Default")
      (node (ref "Q10") (pin "6") (pinfunction "D_6") (pintype "passive"))
      (node (ref "Q10") (pin "P1") (pinfunction "D_P1") (pintype "passive"))
      (node (ref "R25") (pin "1") (pinfunction "1_1") (pintype "passive"))
    )
    (net (code "58") (name "Net-(Q10A-G)") (class "Default")
      (node (ref "Q10") (pin "2") (pinfunction "G_2") (pintype "passive"))
      (node (ref "U3") (pin "10") (pinfunction "Y5_10") (pintype "output"))
    )
    (net (code "59") (name "Net-(Q10B-D-Pad3)") (class "Default")
      (node (ref "Q10") (pin "3") (pinfunction "D_3") (pintype "passive"))
      (node (ref "Q10") (pin "P2") (pinfunction "D_P2") (pintype "passive"))
      (node (ref "R34") (pin "1") (pinfunction "1_1") (pintype "passive"))
    )
    (net (code "60") (name "Net-(Q10B-G)") (class "Default")
      (node (ref "Q10") (pin "5") (pinfunction "G_5") (pintype "passive"))
      (node (ref "U4") (pin "10") (pinfunction "Y5_10") (pintype "output"))
    )
    (net (code "61") (name "Net-(Q11A-D-Pad6)") (class "Default")
      (node (ref "Q11") (pin "6") (pinfunction "D_6") (pintype "passive"))
      (node (ref "Q11") (pin "P1") (pinfunction "D_P1") (pintype "passive"))
      (node (ref "R26") (pin "1") (pinfunction "1_1") (pintype "passive"))
    )
    (net (code "62") (name "Net-(Q11A-G)") (class "Default")
      (node (ref "Q11") (pin "2") (pinfunction "G_2") (pintype "passive"))
      (node (ref "U3") (pin "9") (pinfunction "Y6_9") (pintype "output"))
    )
    (net (code "63") (name "Net-(Q11B-D-Pad3)") (class "Default")
      (node (ref "Q11") (pin "3") (pinfunction "D_3") (pintype "passive"))
      (node (ref "Q11") (pin "P2") (pinfunction "D_P2") (pintype "passive"))
      (node (ref "R35") (pin "1") (pinfunction "1_1") (pintype "passive"))
    )
    (net (code "64") (name "Net-(Q11B-G)") (class "Default")
      (node (ref "Q11") (pin "5") (pinfunction "G_5") (pintype "passive"))
      (node (ref "U4") (pin "9") (pinfunction "Y6_9") (pintype "output"))
    )
    (net (code "65") (name "Net-(Q12A-D-Pad6)") (class "Default")
      (node (ref "Q12") (pin "6") (pinfunction "D_6") (pintype "passive"))
      (node (ref "Q12") (pin "P1") (pinfunction "D_P1") (pintype "passive"))
      (node (ref "R27") (pin "1") (pinfunction "1_1") (pintype "passive"))
    )
    (net (code "66") (name "Net-(Q12A-G)") (class "Default")
      (node (ref "Q12") (pin "2") (pinfunction "G_2") (pintype "passive"))
      (node (ref "U3") (pin "7") (pinfunction "Y7_7") (pintype "output"))
    )
    (net (code "67") (name "Net-(Q12B-D-Pad3)") (class "Default")
      (node (ref "Q12") (pin "3") (pinfunction "D_3") (pintype "passive"))
      (node (ref "Q12") (pin "P2") (pinfunction "D_P2") (pintype "passive"))
      (node (ref "R36") (pin "1") (pinfunction "1_1") (pintype "passive"))
    )
    (net (code "68") (name "Net-(Q12B-G)") (class "Default")
      (node (ref "Q12") (pin "5") (pinfunction "G_5") (pintype "passive"))
      (node (ref "U4") (pin "7") (pinfunction "Y7_7") (pintype "output"))
    )
    (net (code "69") (name "Net-(U1-ADJ)") (class "Default")
      (node (ref "C5") (pin "2") (pinfunction "2_2") (pintype "passive"))
      (node (ref "R1") (pin "1") (pinfunction "1_1") (pintype "passive"))
      (node (ref "R2") (pin "2") (pinfunction "2_2") (pintype "passive"))
      (node (ref "U1") (pin "3") (pinfunction "ADJ_3") (pintype "input"))
    )
    (net (code "70") (name "Net-(U1-EN)") (class "Default")
      (node (ref "C1") (pin "P") (pinfunction "P_P") (pintype "passive"))
      (node (ref "C2") (pin "1") (pinfunction "1_1") (pintype "passive"))
      (node (ref "C3") (pin "1") (pinfunction "1_1") (pintype "passive"))
      (node (ref "F1") (pin "2") (pinfunction "2_2") (pintype "bidirectional"))
      (node (ref "TP1") (pin "P$1") (pinfunction "P$1_P$1") (pintype "bidirectional"))
      (node (ref "U1") (pin "10") (pinfunction "VIN_10") (pintype "power_in"))
      (node (ref "U1") (pin "7") (pinfunction "EN_7") (pintype "input"))
      (node (ref "U1") (pin "9") (pinfunction "VIN_9") (pintype "power_in"))
    )
    (net (code "71") (name "Net-(U1-SS)") (class "Default")
      (node (ref "C4") (pin "1") (pinfunction "1_1") (pintype "passive"))
      (node (ref "U1") (pin "6") (pinfunction "SS_6") (pintype "bidirectional"))
    )
    (net (code "72") (name "PWR0") (class "Default")
      (node (ref "J1") (pin "B15") (pinfunction "29_B15") (pintype "passive"))
      (node (ref "R3") (pin "2") (pinfunction "2_2") (pintype "passive"))
      (node (ref "U2") (pin "1") (pinfunction "A_1") (pintype "input"))
    )
    (net (code "73") (name "PWR1") (class "Default")
      (node (ref "J1") (pin "B16") (pinfunction "31_B16") (pintype "passive"))
      (node (ref "R4") (pin "2") (pinfunction "2_2") (pintype "passive"))
      (node (ref "U2") (pin "2") (pinfunction "B_2") (pintype "input"))
    )
    (net (code "74") (name "PWR2") (class "Default")
      (node (ref "J1") (pin "B17") (pinfunction "33_B17") (pintype "passive"))
      (node (ref "R5") (pin "2") (pinfunction "2_2") (pintype "passive"))
      (node (ref "U2") (pin "3") (pinfunction "C_3") (pintype "input"))
    )
    (net (code "75") (name "ROW0") (class "Default")
      (node (ref "J1") (pin "B5") (pinfunction "9_B5") (pintype "passive"))
      (node (ref "U3") (pin "1") (pinfunction "A_1") (pintype "input"))
      (node (ref "U4") (pin "1") (pinfunction "A_1") (pintype "input"))
    )
    (net (code "76") (name "ROW1") (class "Default")
      (node (ref "J1") (pin "B6") (pinfunction "11_B6") (pintype "passive"))
      (node (ref "U3") (pin "2") (pinfunction "B_2") (pintype "input"))
      (node (ref "U4") (pin "2") (pinfunction "B_2") (pintype "input"))
    )
    (net (code "77") (name "ROW2") (class "Default")
      (node (ref "J1") (pin "B7") (pinfunction "13_B7") (pintype "passive"))
      (node (ref "U3") (pin "3") (pinfunction "C_3") (pintype "input"))
      (node (ref "U4") (pin "3") (pinfunction "C_3") (pintype "input"))
    )
    (net (code "78") (name "V4P2") (class "Default")
      (node (ref "C10") (pin "1") (pinfunction "1_1") (pintype "passive"))
      (node (ref "C11") (pin "1") (pinfunction "1_1") (pintype "passive"))
      (node (ref "C5") (pin "1") (pinfunction "1_1") (pintype "passive"))
      (node (ref "C6") (pin "1") (pinfunction "1_1") (pintype "passive"))
      (node (ref "C7") (pin "1") (pinfunction "1_1") (pintype "passive"))
      (node (ref "C8") (pin "1") (pinfunction "1_1") (pintype "passive"))
      (node (ref "C9") (pin "1") (pinfunction "1_1") (pintype "passive"))
      (node (ref "Q1") (pin "1") (pinfunction "S_1") (pintype "passive"))
      (node (ref "Q1") (pin "4") (pinfunction "S_4") (pintype "passive"))
      (node (ref "Q2") (pin "1") (pinfunction "S_1") (pintype "passive"))
      (node (ref "Q2") (pin "4") (pinfunction "S_4") (pintype "passive"))
      (node (ref "Q3") (pin "1") (pinfunction "S_1") (pintype "passive"))
      (node (ref "Q3") (pin "4") (pinfunction "S_4") (pintype "passive"))
      (node (ref "Q4") (pin "1") (pinfunction "S_1") (pintype "passive"))
      (node (ref "Q4") (pin "4") (pinfunction "S_4") (pintype "passive"))
      (node (ref "R1") (pin "2") (pinfunction "2_2") (pintype "passive"))
      (node (ref "TP2") (pin "P$1") (pinfunction "P$1_P$1") (pintype "bidirectional"))
      (node (ref "U1") (pin "1") (pinfunction "VOUT_1") (pintype "power_in"))
      (node (ref "U1") (pin "2") (pinfunction "VOUT_2") (pintype "power_in"))
      (node (ref "U2") (pin "16") (pinfunction "VCC_16") (pintype "power_in"))
      (node (ref "U2") (pin "6") (pinfunction "G1_6") (pintype "input"))
      (node (ref "U3") (pin "16") (pinfunction "VCC_16") (pintype "power_in"))
      (node (ref "U4") (pin "16") (pinfunction "VCC_16") (pintype "power_in"))
    )
    (net (code "79") (name "V5P0_IN") (class "Default")
      (node (ref "J1") (pin "A1") (pinfunction "2_A1") (pintype "passive"))
      (node (ref "J1") (pin "A3") (pinfunction "6_A3") (pintype "passive"))
      (node (ref "J1") (pin "B1") (pinfunction "1_B1") (pintype "passive"))
      (node (ref "J1") (pin "B3") (pinfunction "5_B3") (pintype "passive"))
      (node (ref "LF1") (pin "1") (pinfunction "P$1_1") (pintype "bidirectional"))
    )
    (net (code "80") (name "VLED") (class "Default")
      (node (ref "D1") (pin "C") (pinfunction "C_C") (pintype "bidirectional"))
      (node (ref "D10") (pin "C") (pinfunction "C_C") (pintype "bidirectional"))
      (node (ref "D11") (pin "C") (pinfunction "C_C") (pintype "bidirectional"))
      (node (ref "D12") (pin "C") (pinfunction "C_C") (pintype "bidirectional"))
      (node (ref "D13") (pin "C") (pinfunction "C_C") (pintype "bidirectional"))
      (node (ref "D14") (pin "C") (pinfunction "C_C") (pintype "bidirectional"))
      (node (ref "D15") (pin "C") (pinfunction "C_C") (pintype "bidirectional"))
      (node (ref "D16") (pin "C") (pinfunction "C_C") (pintype "bidirectional"))
      (node (ref "D2") (pin "C") (pinfunction "C_C") (pintype "bidirectional"))
      (node (ref "D3") (pin "C") (pinfunction "C_C") (pintype "bidirectional"))
      (node (ref "D4") (pin "C") (pinfunction "C_C") (pintype "bidirectional"))
      (node (ref "D5") (pin "C") (pinfunction "C_C") (pintype "bidirectional"))
      (node (ref "D6") (pin "C") (pinfunction "C_C") (pintype "bidirectional"))
      (node (ref "D7") (pin "C") (pinfunction "C_C") (pintype "bidirectional"))
      (node (ref "D8") (pin "C") (pinfunction "C_C") (pintype "bidirectional"))
      (node (ref "D9") (pin "C") (pinfunction "C_C") (pintype "bidirectional"))
      (node (ref "J2") (pin "14") (pinfunction "14_14") (pintype "passive"))
      (node (ref "J2") (pin "15") (pinfunction "15_15") (pintype "passive"))
      (node (ref "J2") (pin "2") (pinfunction "2_2") (pintype "passive"))
      (node (ref "J2") (pin "20") (pinfunction "20_20") (pintype "passive"))
      (node (ref "J2") (pin "21") (pinfunction "21_21") (pintype "passive"))
      (node (ref "J2") (pin "26") (pinfunction "26_26") (pintype "passive"))
      (node (ref "J2") (pin "3") (pinfunction "3_3") (pintype "passive"))
      (node (ref "J2") (pin "8") (pinfunction "8_8") (pintype "passive"))
      (node (ref "J2") (pin "9") (pinfunction "9_9") (pintype "passive"))
      (node (ref "R10") (pin "1") (pinfunction "1_1") (pintype "passive"))
      (node (ref "R11") (pin "1") (pinfunction "1_1") (pintype "passive"))
      (node (ref "R12") (pin "1") (pinfunction "1_1") (pintype "passive"))
      (node (ref "R13") (pin "1") (pinfunction "1_1") (pintype "passive"))
      (node (ref "R14") (pin "1") (pinfunction "1_1") (pintype "passive"))
      (node (ref "R15") (pin "1") (pinfunction "1_1") (pintype "passive"))
      (node (ref "R16") (pin "1") (pinfunction "1_1") (pintype "passive"))
      (node (ref "R17") (pin "1") (pinfunction "1_1") (pintype "passive"))
      (node (ref "R18") (pin "2") (pinfunction "2_2") (pintype "passive"))
      (node (ref "R6") (pin "1") (pinfunction "1_1") (pintype "passive"))
      (node (ref "R7") (pin "1") (pinfunction "1_1") (pintype "passive"))
      (node (ref "R8") (pin "1") (pinfunction "1_1") (pintype "passive"))
      (node (ref "R9") (pin "1") (pinfunction "1_1") (pintype "passive"))
      (node (ref "TP3") (pin "P$1") (pinfunction "P$1_P$1") (pintype "bidirectional"))
    )
    (net (code "81") (name "unconnected-(J1-15-PadB8)") (class "Default")
      (node (ref "J1") (pin "B8") (pinfunction "15_B8") (pintype "passive"))
    )
    (net (code "82") (name "unconnected-(J1-17-PadB9)") (class "Default")
      (node (ref "J1") (pin "B9") (pinfunction "17_B9") (pintype "passive"))
    )
    (net (code "83") (name "unconnected-(J1-19-PadB10)") (class "Default")
      (node (ref "J1") (pin "B10") (pinfunction "19_B10") (pintype "passive"))
    )
    (net (code "84") (name "unconnected-(J1-21-PadB11)") (class "Default")
      (node (ref "J1") (pin "B11") (pinfunction "21_B11") (pintype "passive"))
    )
    (net (code "85") (name "unconnected-(J1-23-PadB12)") (class "Default")
      (node (ref "J1") (pin "B12") (pinfunction "23_B12") (pintype "passive"))
    )
    (net (code "86") (name "unconnected-(J1-30-PadA15)") (class "Default")
      (node (ref "J1") (pin "A15") (pinfunction "30_A15") (pintype "passive"))
    )
    (net (code "87") (name "unconnected-(J1-34-PadA17)") (class "Default")
      (node (ref "J1") (pin "A17") (pinfunction "34_A17") (pintype "passive"))
    )
    (net (code "88") (name "unconnected-(J1-36-PadA18)") (class "Default")
      (node (ref "J1") (pin "A18") (pinfunction "36_A18") (pintype "passive"))
    )
    (net (code "89") (name "unconnected-(J1-38-PadA19)") (class "Default")
      (node (ref "J1") (pin "A19") (pinfunction "38_A19") (pintype "passive"))
    )
    (net (code "90") (name "unconnected-(J1-39-PadB20)") (class "Default")
      (node (ref "J1") (pin "B20") (pinfunction "39_B20") (pintype "passive"))
    )
  )
)
